# murdock_top_v2.net
KiCad netlist of a schematic drawn in EAGLE
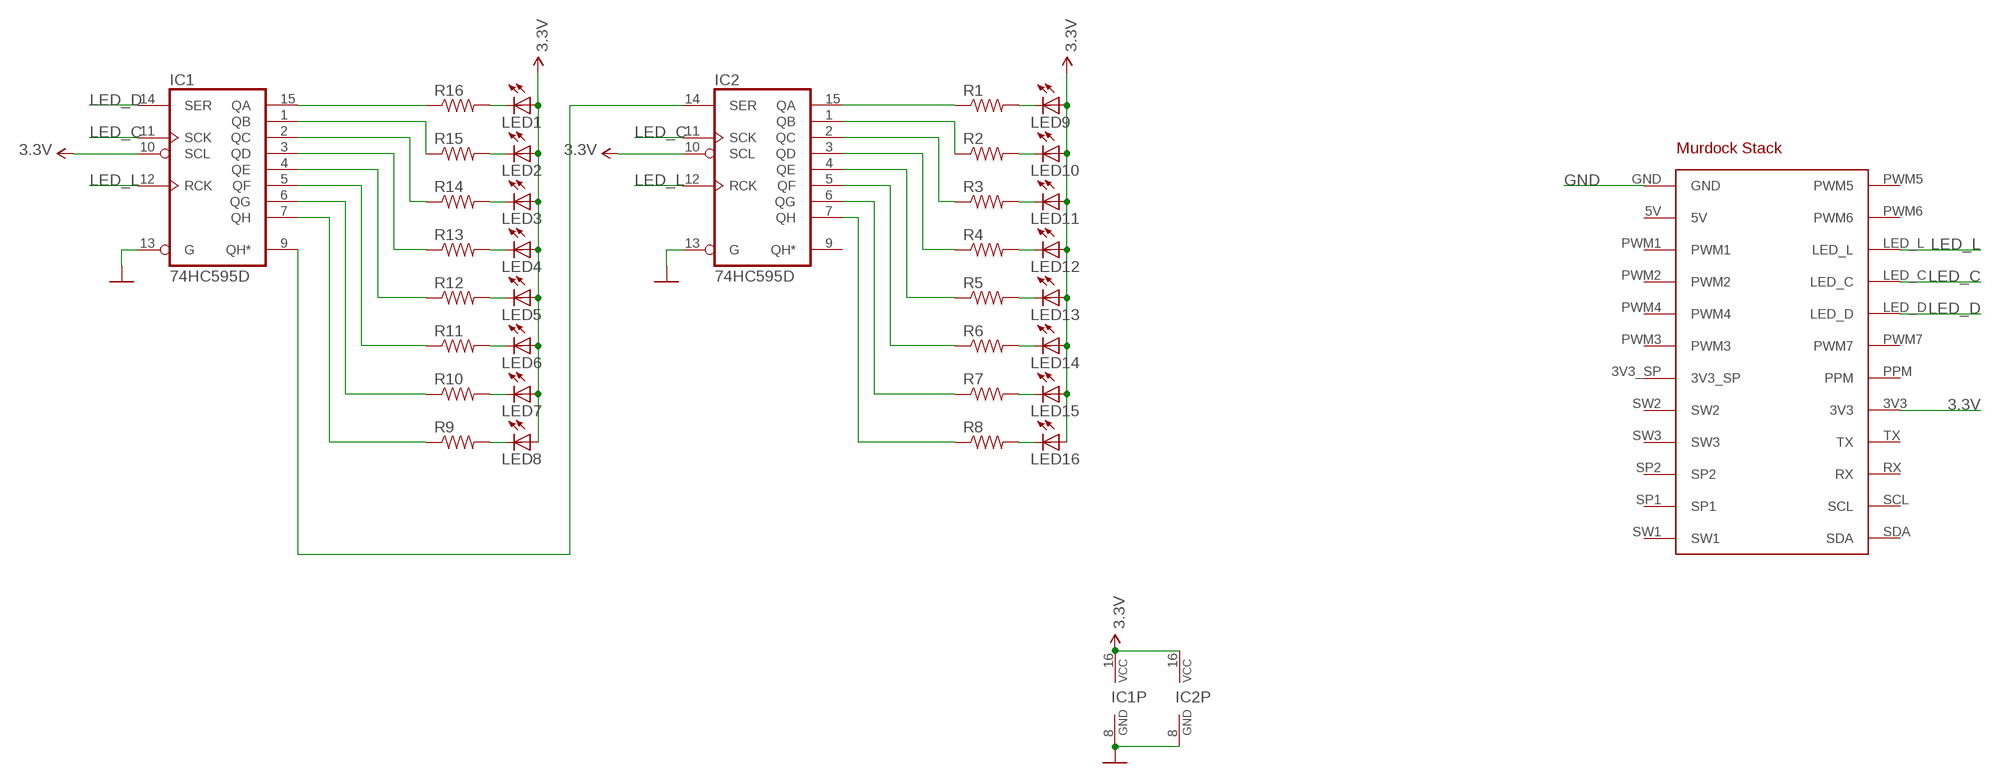
[diagram p0: schematic, sheet 1]

(export (version "E")
  (design (tool "Eeschema 10.0.6"))
  (components
    (comp (ref "IC1")
      (value "74HC595D")
      (footprint "eagle-import:SO16")
      (libsource (lib "eagle-import") (part "74595DHC"))
    )
    (comp (ref "IC2")
      (value "74HC595D")
      (footprint "eagle-import:SO16")
      (libsource (lib "eagle-import") (part "74595DHC"))
    )
    (comp (ref "LED1")
      (value "LGM47K")
      (footprint "eagle-import:LGM47K")
      (libsource (lib "eagle-import") (part "LGM47K"))
    )
    (comp (ref "LED2")
      (value "LGM47K")
      (footprint "eagle-import:LGM47K")
      (libsource (lib "eagle-import") (part "LGM47K"))
    )
    (comp (ref "LED3")
      (value "LGM47K")
      (footprint "eagle-import:LGM47K")
      (libsource (lib "eagle-import") (part "LGM47K"))
    )
    (comp (ref "LED4")
      (value "LGM47K")
      (footprint "eagle-import:LGM47K")
      (libsource (lib "eagle-import") (part "LGM47K"))
    )
    (comp (ref "LED5")
      (value "LGM47K")
      (footprint "eagle-import:LGM47K")
      (libsource (lib "eagle-import") (part "LGM47K"))
    )
    (comp (ref "LED6")
      (value "LGM47K")
      (footprint "eagle-import:LGM47K")
      (libsource (lib "eagle-import") (part "LGM47K"))
    )
    (comp (ref "LED7")
      (value "LGM47K")
      (footprint "eagle-import:LGM47K")
      (libsource (lib "eagle-import") (part "LGM47K"))
    )
    (comp (ref "LED8")
      (value "LGM47K")
      (footprint "eagle-import:LGM47K")
      (libsource (lib "eagle-import") (part "LGM47K"))
    )
    (comp (ref "LED9")
      (value "LGM47K")
      (footprint "eagle-import:LGM47K")
      (libsource (lib "eagle-import") (part "LGM47K"))
    )
    (comp (ref "LED10")
      (value "LGM47K")
      (footprint "eagle-import:LGM47K")
      (libsource (lib "eagle-import") (part "LGM47K"))
    )
    (comp (ref "LED11")
      (value "LGM47K")
      (footprint "eagle-import:LGM47K")
      (libsource (lib "eagle-import") (part "LGM47K"))
    )
    (comp (ref "LED12")
      (value "LGM47K")
      (footprint "eagle-import:LGM47K")
      (libsource (lib "eagle-import") (part "LGM47K"))
    )
    (comp (ref "LED13")
      (value "LGM47K")
      (footprint "eagle-import:LGM47K")
      (libsource (lib "eagle-import") (part "LGM47K"))
    )
    (comp (ref "LED14")
      (value "LGM47K")
      (footprint "eagle-import:LGM47K")
      (libsource (lib "eagle-import") (part "LGM47K"))
    )
    (comp (ref "LED15")
      (value "LGM47K")
      (footprint "eagle-import:LGM47K")
      (libsource (lib "eagle-import") (part "LGM47K"))
    )
    (comp (ref "LED16")
      (value "LGM47K")
      (footprint "eagle-import:LGM47K")
      (libsource (lib "eagle-import") (part "LGM47K"))
    )
    (comp (ref "R1")
      (value "RESISTOR0402-RES")
      (footprint "eagle-import:0402-RES")
      (libsource (lib "eagle-import") (part "RESISTOR0402-RES"))
    )
    (comp (ref "R2")
      (value "RESISTOR0402-RES")
      (footprint "eagle-import:0402-RES")
      (libsource (lib "eagle-import") (part "RESISTOR0402-RES"))
    )
    (comp (ref "R3")
      (value "RESISTOR0402-RES")
      (footprint "eagle-import:0402-RES")
      (libsource (lib "eagle-import") (part "RESISTOR0402-RES"))
    )
    (comp (ref "R4")
      (value "RESISTOR0402-RES")
      (footprint "eagle-import:0402-RES")
      (libsource (lib "eagle-import") (part "RESISTOR0402-RES"))
    )
    (comp (ref "R5")
      (value "RESISTOR0402-RES")
      (footprint "eagle-import:0402-RES")
      (libsource (lib "eagle-import") (part "RESISTOR0402-RES"))
    )
    (comp (ref "R6")
      (value "RESISTOR0402-RES")
      (footprint "eagle-import:0402-RES")
      (libsource (lib "eagle-import") (part "RESISTOR0402-RES"))
    )
    (comp (ref "R7")
      (value "RESISTOR0402-RES")
      (footprint "eagle-import:0402-RES")
      (libsource (lib "eagle-import") (part "RESISTOR0402-RES"))
    )
    (comp (ref "R8")
      (value "RESISTOR0402-RES")
      (footprint "eagle-import:0402-RES")
      (libsource (lib "eagle-import") (part "RESISTOR0402-RES"))
    )
    (comp (ref "R9")
      (value "RESISTOR0402-RES")
      (footprint "eagle-import:0402-RES")
      (libsource (lib "eagle-import") (part "RESISTOR0402-RES"))
    )
    (comp (ref "R10")
      (value "RESISTOR0402-RES")
      (footprint "eagle-import:0402-RES")
      (libsource (lib "eagle-import") (part "RESISTOR0402-RES"))
    )
    (comp (ref "R11")
      (value "RESISTOR0402-RES")
      (footprint "eagle-import:0402-RES")
      (libsource (lib "eagle-import") (part "RESISTOR0402-RES"))
    )
    (comp (ref "R12")
      (value "RESISTOR0402-RES")
      (footprint "eagle-import:0402-RES")
      (libsource (lib "eagle-import") (part "RESISTOR0402-RES"))
    )
    (comp (ref "R13")
      (value "RESISTOR0402-RES")
      (footprint "eagle-import:0402-RES")
      (libsource (lib "eagle-import") (part "RESISTOR0402-RES"))
    )
    (comp (ref "R14")
      (value "RESISTOR0402-RES")
      (footprint "eagle-import:0402-RES")
      (libsource (lib "eagle-import") (part "RESISTOR0402-RES"))
    )
    (comp (ref "R15")
      (value "RESISTOR0402-RES")
      (footprint "eagle-import:0402-RES")
      (libsource (lib "eagle-import") (part "RESISTOR0402-RES"))
    )
    (comp (ref "R16")
      (value "RESISTOR0402-RES")
      (footprint "eagle-import:0402-RES")
      (libsource (lib "eagle-import") (part "RESISTOR0402-RES"))
    )
    (comp (ref "X1")
      (value "MURDOCK_STACK")
      (footprint "eagle-import:MURDOCK_STACK")
      (libsource (lib "eagle-import") (part "MURDOCK_STACK"))
    )
  )
  (nets
    (net (code "1") (name "/LED_C") (class "Default")
      (node (ref "IC1") (pin "11") (pinfunction "SCK_11") (pintype "input"))
      (node (ref "IC2") (pin "11") (pinfunction "SCK_11") (pintype "input"))
      (node (ref "X1") (pin "LED_C") (pinfunction "LED_C_LED_C") (pintype "bidirectional"))
    )
    (net (code "2") (name "/LED_D") (class "Default")
      (node (ref "IC1") (pin "14") (pinfunction "SER_14") (pintype "input"))
      (node (ref "X1") (pin "LED_D") (pinfunction "LED_D_LED_D") (pintype "bidirectional"))
    )
    (net (code "3") (name "/LED_L") (class "Default")
      (node (ref "IC1") (pin "12") (pinfunction "RCK_12") (pintype "input"))
      (node (ref "IC2") (pin "12") (pinfunction "RCK_12") (pintype "input"))
      (node (ref "X1") (pin "LED_L") (pinfunction "LED_L_LED_L") (pintype "bidirectional"))
    )
    (net (code "4") (name "3.3V") (class "Default")
      (node (ref "IC1") (pin "10") (pinfunction "SCL_10") (pintype "input"))
      (node (ref "IC1") (pin "16") (pinfunction "VCC_16") (pintype "power_in"))
      (node (ref "IC2") (pin "10") (pinfunction "SCL_10") (pintype "input"))
      (node (ref "IC2") (pin "16") (pinfunction "VCC_16") (pintype "power_in"))
      (node (ref "LED1") (pin "A") (pinfunction "A_A") (pintype "passive"))
      (node (ref "LED10") (pin "A") (pinfunction "A_A") (pintype "passive"))
      (node (ref "LED11") (pin "A") (pinfunction "A_A") (pintype "passive"))
      (node (ref "LED12") (pin "A") (pinfunction "A_A") (pintype "passive"))
      (node (ref "LED13") (pin "A") (pinfunction "A_A") (pintype "passive"))
      (node (ref "LED14") (pin "A") (pinfunction "A_A") (pintype "passive"))
      (node (ref "LED15") (pin "A") (pinfunction "A_A") (pintype "passive"))
      (node (ref "LED16") (pin "A") (pinfunction "A_A") (pintype "passive"))
      (node (ref "LED2") (pin "A") (pinfunction "A_A") (pintype "passive"))
      (node (ref "LED3") (pin "A") (pinfunction "A_A") (pintype "passive"))
      (node (ref "LED4") (pin "A") (pinfunction "A_A") (pintype "passive"))
      (node (ref "LED5") (pin "A") (pinfunction "A_A") (pintype "passive"))
      (node (ref "LED6") (pin "A") (pinfunction "A_A") (pintype "passive"))
      (node (ref "LED7") (pin "A") (pinfunction "A_A") (pintype "passive"))
      (node (ref "LED8") (pin "A") (pinfunction "A_A") (pintype "passive"))
      (node (ref "LED9") (pin "A") (pinfunction "A_A") (pintype "passive"))
      (node (ref "X1") (pin "3V3") (pinfunction "3V3_3V3") (pintype "bidirectional"))
    )
    (net (code "5") (name "GND") (class "Default")
      (node (ref "IC1") (pin "13") (pinfunction "G_13") (pintype "input"))
      (node (ref "IC1") (pin "8") (pinfunction "GND_8") (pintype "power_in"))
      (node (ref "IC2") (pin "13") (pinfunction "G_13") (pintype "input"))
      (node (ref "IC2") (pin "8") (pinfunction "GND_8") (pintype "power_in"))
      (node (ref "X1") (pin "GND") (pinfunction "GND_GND") (pintype "bidirectional"))
    )
    (net (code "6") (name "Net-(IC1A-QA)") (class "Default")
      (node (ref "IC1") (pin "15") (pinfunction "QA_15") (pintype "tri_state"))
      (node (ref "R16") (pin "1") (pinfunction "1_1") (pintype "passive"))
    )
    (net (code "7") (name "Net-(IC1A-QB)") (class "Default")
      (node (ref "IC1") (pin "1") (pinfunction "QB_1") (pintype "tri_state"))
      (node (ref "R15") (pin "1") (pinfunction "1_1") (pintype "passive"))
    )
    (net (code "8") (name "Net-(IC1A-QC)") (class "Default")
      (node (ref "IC1") (pin "2") (pinfunction "QC_2") (pintype "tri_state"))
      (node (ref "R14") (pin "1") (pinfunction "1_1") (pintype "passive"))
    )
    (net (code "9") (name "Net-(IC1A-QD)") (class "Default")
      (node (ref "IC1") (pin "3") (pinfunction "QD_3") (pintype "tri_state"))
      (node (ref "R13") (pin "1") (pinfunction "1_1") (pintype "passive"))
    )
    (net (code "10") (name "Net-(IC1A-QE)") (class "Default")
      (node (ref "IC1") (pin "4") (pinfunction "QE_4") (pintype "tri_state"))
      (node (ref "R12") (pin "1") (pinfunction "1_1") (pintype "passive"))
    )
    (net (code "11") (name "Net-(IC1A-QF)") (class "Default")
      (node (ref "IC1") (pin "5") (pinfunction "QF_5") (pintype "tri_state"))
      (node (ref "R11") (pin "1") (pinfunction "1_1") (pintype "passive"))
    )
    (net (code "12") (name "Net-(IC1A-QG)") (class "Default")
      (node (ref "IC1") (pin "6") (pinfunction "QG_6") (pintype "tri_state"))
      (node (ref "R10") (pin "1") (pinfunction "1_1") (pintype "passive"))
    )
    (net (code "13") (name "Net-(IC1A-QH)") (class "Default")
      (node (ref "IC1") (pin "7") (pinfunction "QH_7") (pintype "tri_state"))
      (node (ref "R9") (pin "1") (pinfunction "1_1") (pintype "passive"))
    )
    (net (code "14") (name "Net-(IC1A-QH*)") (class "Default")
      (node (ref "IC1") (pin "9") (pinfunction "QH*_9") (pintype "tri_state"))
      (node (ref "IC2") (pin "14") (pinfunction "SER_14") (pintype "input"))
    )
    (net (code "15") (name "Net-(IC2A-QA)") (class "Default")
      (node (ref "IC2") (pin "15") (pinfunction "QA_15") (pintype "tri_state"))
      (node (ref "R1") (pin "1") (pinfunction "1_1") (pintype "passive"))
    )
    (net (code "16") (name "Net-(IC2A-QB)") (class "Default")
      (node (ref "IC2") (pin "1") (pinfunction "QB_1") (pintype "tri_state"))
      (node (ref "R2") (pin "1") (pinfunction "1_1") (pintype "passive"))
    )
    (net (code "17") (name "Net-(IC2A-QC)") (class "Default")
      (node (ref "IC2") (pin "2") (pinfunction "QC_2") (pintype "tri_state"))
      (node (ref "R3") (pin "1") (pinfunction "1_1") (pintype "passive"))
    )
    (net (code "18") (name "Net-(IC2A-QD)") (class "Default")
      (node (ref "IC2") (pin "3") (pinfunction "QD_3") (pintype "tri_state"))
      (node (ref "R4") (pin "1") (pinfunction "1_1") (pintype "passive"))
    )
    (net (code "19") (name "Net-(IC2A-QE)") (class "Default")
      (node (ref "IC2") (pin "4") (pinfunction "QE_4") (pintype "tri_state"))
      (node (ref "R5") (pin "1") (pinfunction "1_1") (pintype "passive"))
    )
    (net (code "20") (name "Net-(IC2A-QF)") (class "Default")
      (node (ref "IC2") (pin "5") (pinfunction "QF_5") (pintype "tri_state"))
      (node (ref "R6") (pin "1") (pinfunction "1_1") (pintype "passive"))
    )
    (net (code "21") (name "Net-(IC2A-QG)") (class "Default")
      (node (ref "IC2") (pin "6") (pinfunction "QG_6") (pintype "tri_state"))
      (node (ref "R7") (pin "1") (pinfunction "1_1") (pintype "passive"))
    )
    (net (code "22") (name "Net-(IC2A-QH)") (class "Default")
      (node (ref "IC2") (pin "7") (pinfunction "QH_7") (pintype "tri_state"))
      (node (ref "R8") (pin "1") (pinfunction "1_1") (pintype "passive"))
    )
    (net (code "23") (name "Net-(LED1-C)") (class "Default")
      (node (ref "LED1") (pin "K") (pinfunction "C_K") (pintype "passive"))
      (node (ref "R16") (pin "2") (pinfunction "2_2") (pintype "passive"))
    )
    (net (code "24") (name "Net-(LED2-C)") (class "Default")
      (node (ref "LED2") (pin "K") (pinfunction "C_K") (pintype "passive"))
      (node (ref "R15") (pin "2") (pinfunction "2_2") (pintype "passive"))
    )
    (net (code "25") (name "Net-(LED3-C)") (class "Default")
      (node (ref "LED3") (pin "K") (pinfunction "C_K") (pintype "passive"))
      (node (ref "R14") (pin "2") (pinfunction "2_2") (pintype "passive"))
    )
    (net (code "26") (name "Net-(LED4-C)") (class "Default")
      (node (ref "LED4") (pin "K") (pinfunction "C_K") (pintype "passive"))
      (node (ref "R13") (pin "2") (pinfunction "2_2") (pintype "passive"))
    )
    (net (code "27") (name "Net-(LED5-C)") (class "Default")
      (node (ref "LED5") (pin "K") (pinfunction "C_K") (pintype "passive"))
      (node (ref "R12") (pin "2") (pinfunction "2_2") (pintype "passive"))
    )
    (net (code "28") (name "Net-(LED6-C)") (class "Default")
      (node (ref "LED6") (pin "K") (pinfunction "C_K") (pintype "passive"))
      (node (ref "R11") (pin "2") (pinfunction "2_2") (pintype "passive"))
    )
    (net (code "29") (name "Net-(LED7-C)") (class "Default")
      (node (ref "LED7") (pin "K") (pinfunction "C_K") (pintype "passive"))
      (node (ref "R10") (pin "2") (pinfunction "2_2") (pintype "passive"))
    )
    (net (code "30") (name "Net-(LED8-C)") (class "Default")
      (node (ref "LED8") (pin "K") (pinfunction "C_K") (pintype "passive"))
      (node (ref "R9") (pin "2") (pinfunction "2_2") (pintype "passive"))
    )
    (net (code "31") (name "Net-(LED9-C)") (class "Default")
      (node (ref "LED9") (pin "K") (pinfunction "C_K") (pintype "passive"))
      (node (ref "R1") (pin "2") (pinfunction "2_2") (pintype "passive"))
    )
    (net (code "32") (name "Net-(LED10-C)") (class "Default")
      (node (ref "LED10") (pin "K") (pinfunction "C_K") (pintype "passive"))
      (node (ref "R2") (pin "2") (pinfunction "2_2") (pintype "passive"))
    )
    (net (code "33") (name "Net-(LED11-C)") (class "Default")
      (node (ref "LED11") (pin "K") (pinfunction "C_K") (pintype "passive"))
      (node (ref "R3") (pin "2") (pinfunction "2_2") (pintype "passive"))
    )
    (net (code "34") (name "Net-(LED12-C)") (class "Default")
      (node (ref "LED12") (pin "K") (pinfunction "C_K") (pintype "passive"))
      (node (ref "R4") (pin "2") (pinfunction "2_2") (pintype "passive"))
    )
    (net (code "35") (name "Net-(LED13-C)") (class "Default")
      (node (ref "LED13") (pin "K") (pinfunction "C_K") (pintype "passive"))
      (node (ref "R5") (pin "2") (pinfunction "2_2") (pintype "passive"))
    )
    (net (code "36") (name "Net-(LED14-C)") (class "Default")
      (node (ref "LED14") (pin "K") (pinfunction "C_K") (pintype "passive"))
      (node (ref "R6") (pin "2") (pinfunction "2_2") (pintype "passive"))
    )
    (net (code "37") (name "Net-(LED15-C)") (class "Default")
      (node (ref "LED15") (pin "K") (pinfunction "C_K") (pintype "passive"))
      (node (ref "R7") (pin "2") (pinfunction "2_2") (pintype "passive"))
    )
    (net (code "38") (name "Net-(LED16-C)") (class "Default")
      (node (ref "LED16") (pin "K") (pinfunction "C_K") (pintype "passive"))
      (node (ref "R8") (pin "2") (pinfunction "2_2") (pintype "passive"))
    )
    (net (code "39") (name "unconnected-(IC2A-QH*-Pad9)") (class "Default")
      (node (ref "IC2") (pin "9") (pinfunction "QH*_9") (pintype "tri_state"))
    )
    (net (code "40") (name "unconnected-(X1-Pad3V3_SP)") (class "Default")
      (node (ref "X1") (pin "3V3_SP") (pinfunction "3V3_SP_3V3_SP") (pintype "bidirectional"))
    )
    (net (code "41") (name "unconnected-(X1-Pad5V)") (class "Default")
      (node (ref "X1") (pin "5V") (pinfunction "5V_5V") (pintype "bidirectional"))
    )
    (net (code "42") (name "unconnected-(X1-PadPPM)") (class "Default")
      (node (ref "X1") (pin "PPM") (pinfunction "PPM_PPM") (pintype "bidirectional"))
    )
    (net (code "43") (name "unconnected-(X1-PadPWM1)") (class "Default")
      (node (ref "X1") (pin "PWM1") (pinfunction "PWM1_PWM1") (pintype "bidirectional"))
    )
    (net (code "44") (name "unconnected-(X1-PadPWM2)") (class "Default")
      (node (ref "X1") (pin "PWM2") (pinfunction "PWM2_PWM2") (pintype "bidirectional"))
    )
    (net (code "45") (name "unconnected-(X1-PadPWM3)") (class "Default")
      (node (ref "X1") (pin "PWM3") (pinfunction "PWM3_PWM3") (pintype "bidirectional"))
    )
    (net (code "46") (name "unconnected-(X1-PadPWM4)") (class "Default")
      (node (ref "X1") (pin "PWM4") (pinfunction "PWM4_PWM4") (pintype "bidirectional"))
    )
    (net (code "47") (name "unconnected-(X1-PadPWM5)") (class "Default")
      (node (ref "X1") (pin "PWM5") (pinfunction "PWM5_PWM5") (pintype "bidirectional"))
    )
    (net (code "48") (name "unconnected-(X1-PadPWM6)") (class "Default")
      (node (ref "X1") (pin "PWM6") (pinfunction "PWM6_PWM6") (pintype "bidirectional"))
    )
    (net (code "49") (name "unconnected-(X1-PadPWM7)") (class "Default")
      (node (ref "X1") (pin "PWM7") (pinfunction "PWM7_PWM7") (pintype "bidirectional"))
    )
    (net (code "50") (name "unconnected-(X1-PadRX)") (class "Default")
      (node (ref "X1") (pin "RX") (pinfunction "RX_RX") (pintype "bidirectional"))
    )
    (net (code "51") (name "unconnected-(X1-PadSCL)") (class "Default")
      (node (ref "X1") (pin "SCL") (pinfunction "SCL_SCL") (pintype "bidirectional"))
    )
    (net (code "52") (name "unconnected-(X1-PadSDA)") (class "Default")
      (node (ref "X1") (pin "SDA") (pinfunction "SDA_SDA") (pintype "bidirectional"))
    )
    (net (code "53") (name "unconnected-(X1-PadSP1)") (class "Default")
      (node (ref "X1") (pin "SP1") (pinfunction "SP1_SP1") (pintype "bidirectional"))
    )
    (net (code "54") (name "unconnected-(X1-PadSP2)") (class "Default")
      (node (ref "X1") (pin "SP2") (pinfunction "SP2_SP2") (pintype "bidirectional"))
    )
    (net (code "55") (name "unconnected-(X1-PadSW1)") (class "Default")
      (node (ref "X1") (pin "SW1") (pinfunction "SW1_SW1") (pintype "bidirectional"))
    )
    (net (code "56") (name "unconnected-(X1-PadSW2)") (class "Default")
      (node (ref "X1") (pin "SW2") (pinfunction "SW2_SW2") (pintype "bidirectional"))
    )
    (net (code "57") (name "unconnected-(X1-PadSW3)") (class "Default")
      (node (ref "X1") (pin "SW3") (pinfunction "SW3_SW3") (pintype "bidirectional"))
    )
    (net (code "58") (name "unconnected-(X1-PadTX)") (class "Default")
      (node (ref "X1") (pin "TX") (pinfunction "TX_TX") (pintype "bidirectional"))
    )
  )
)
